# Front-End.net
KiCad netlist of a schematic drawn in EAGLE
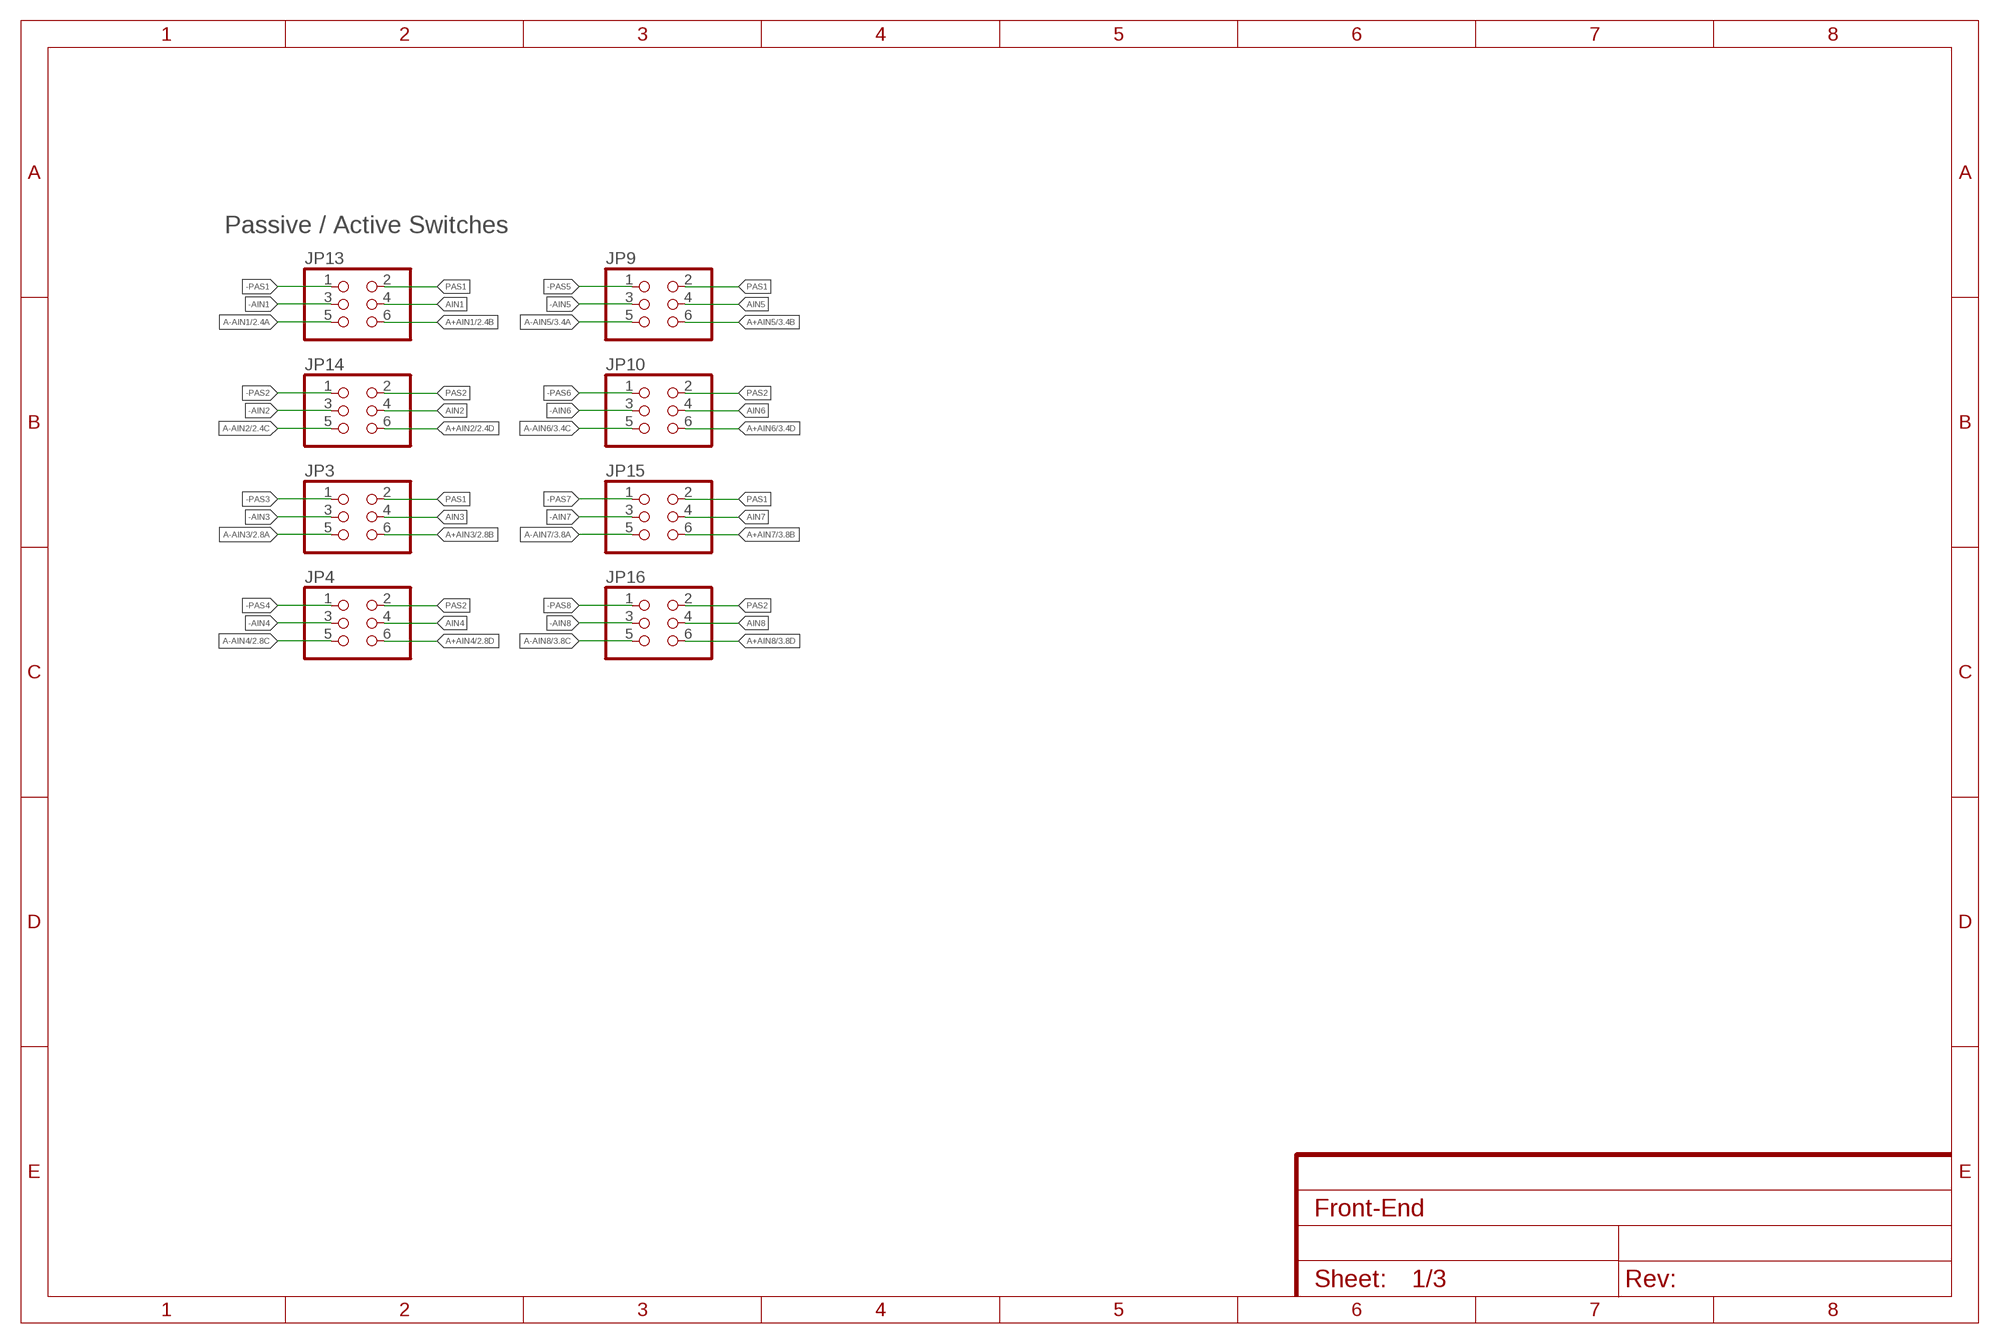
[diagram p0: schematic, sheet 1]
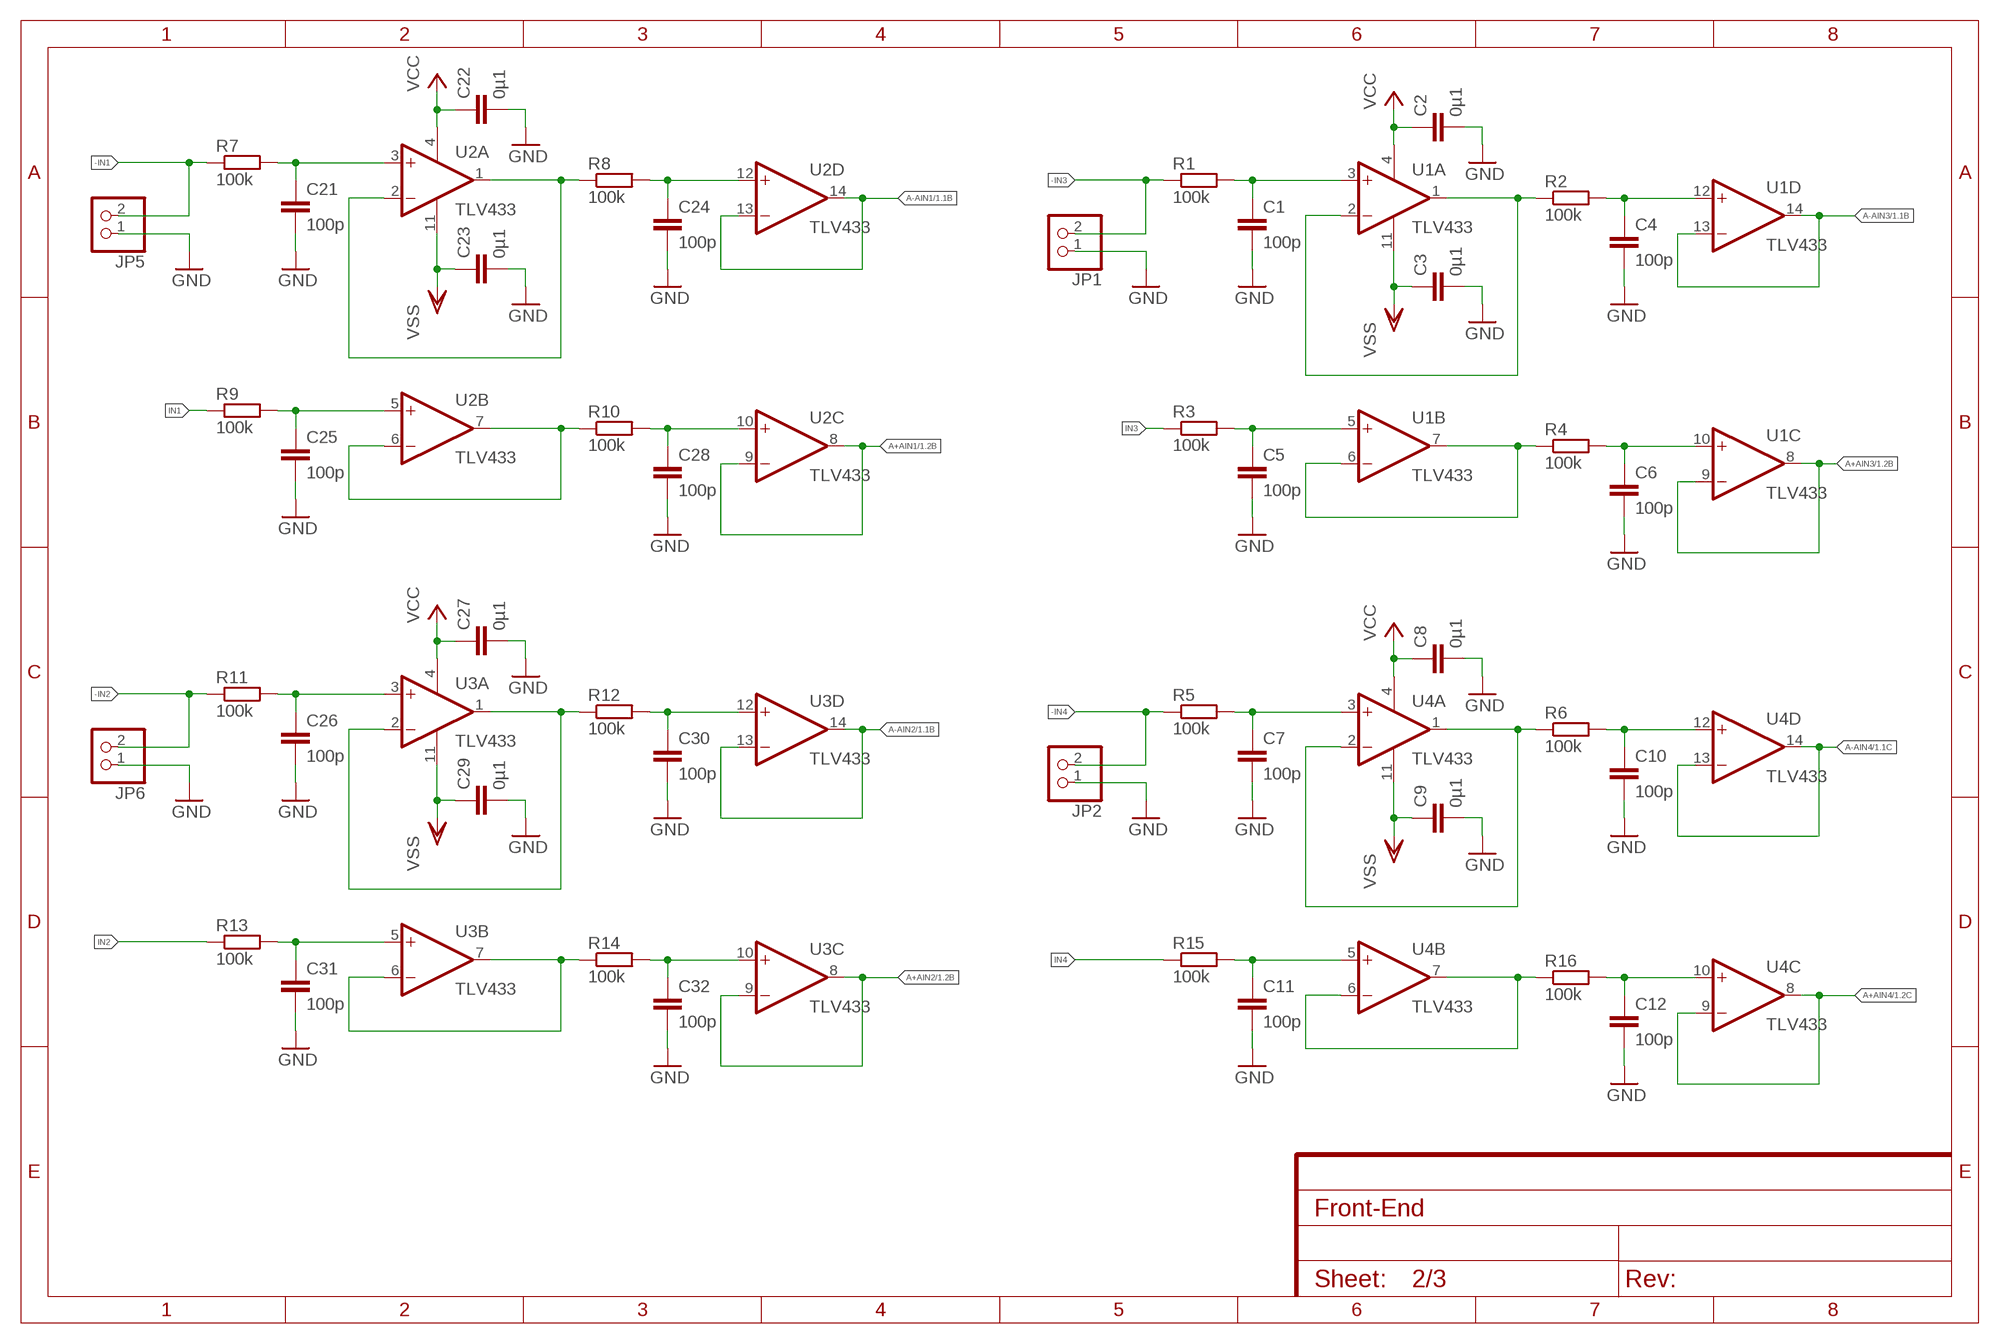
[diagram p1: schematic, sheet 2]
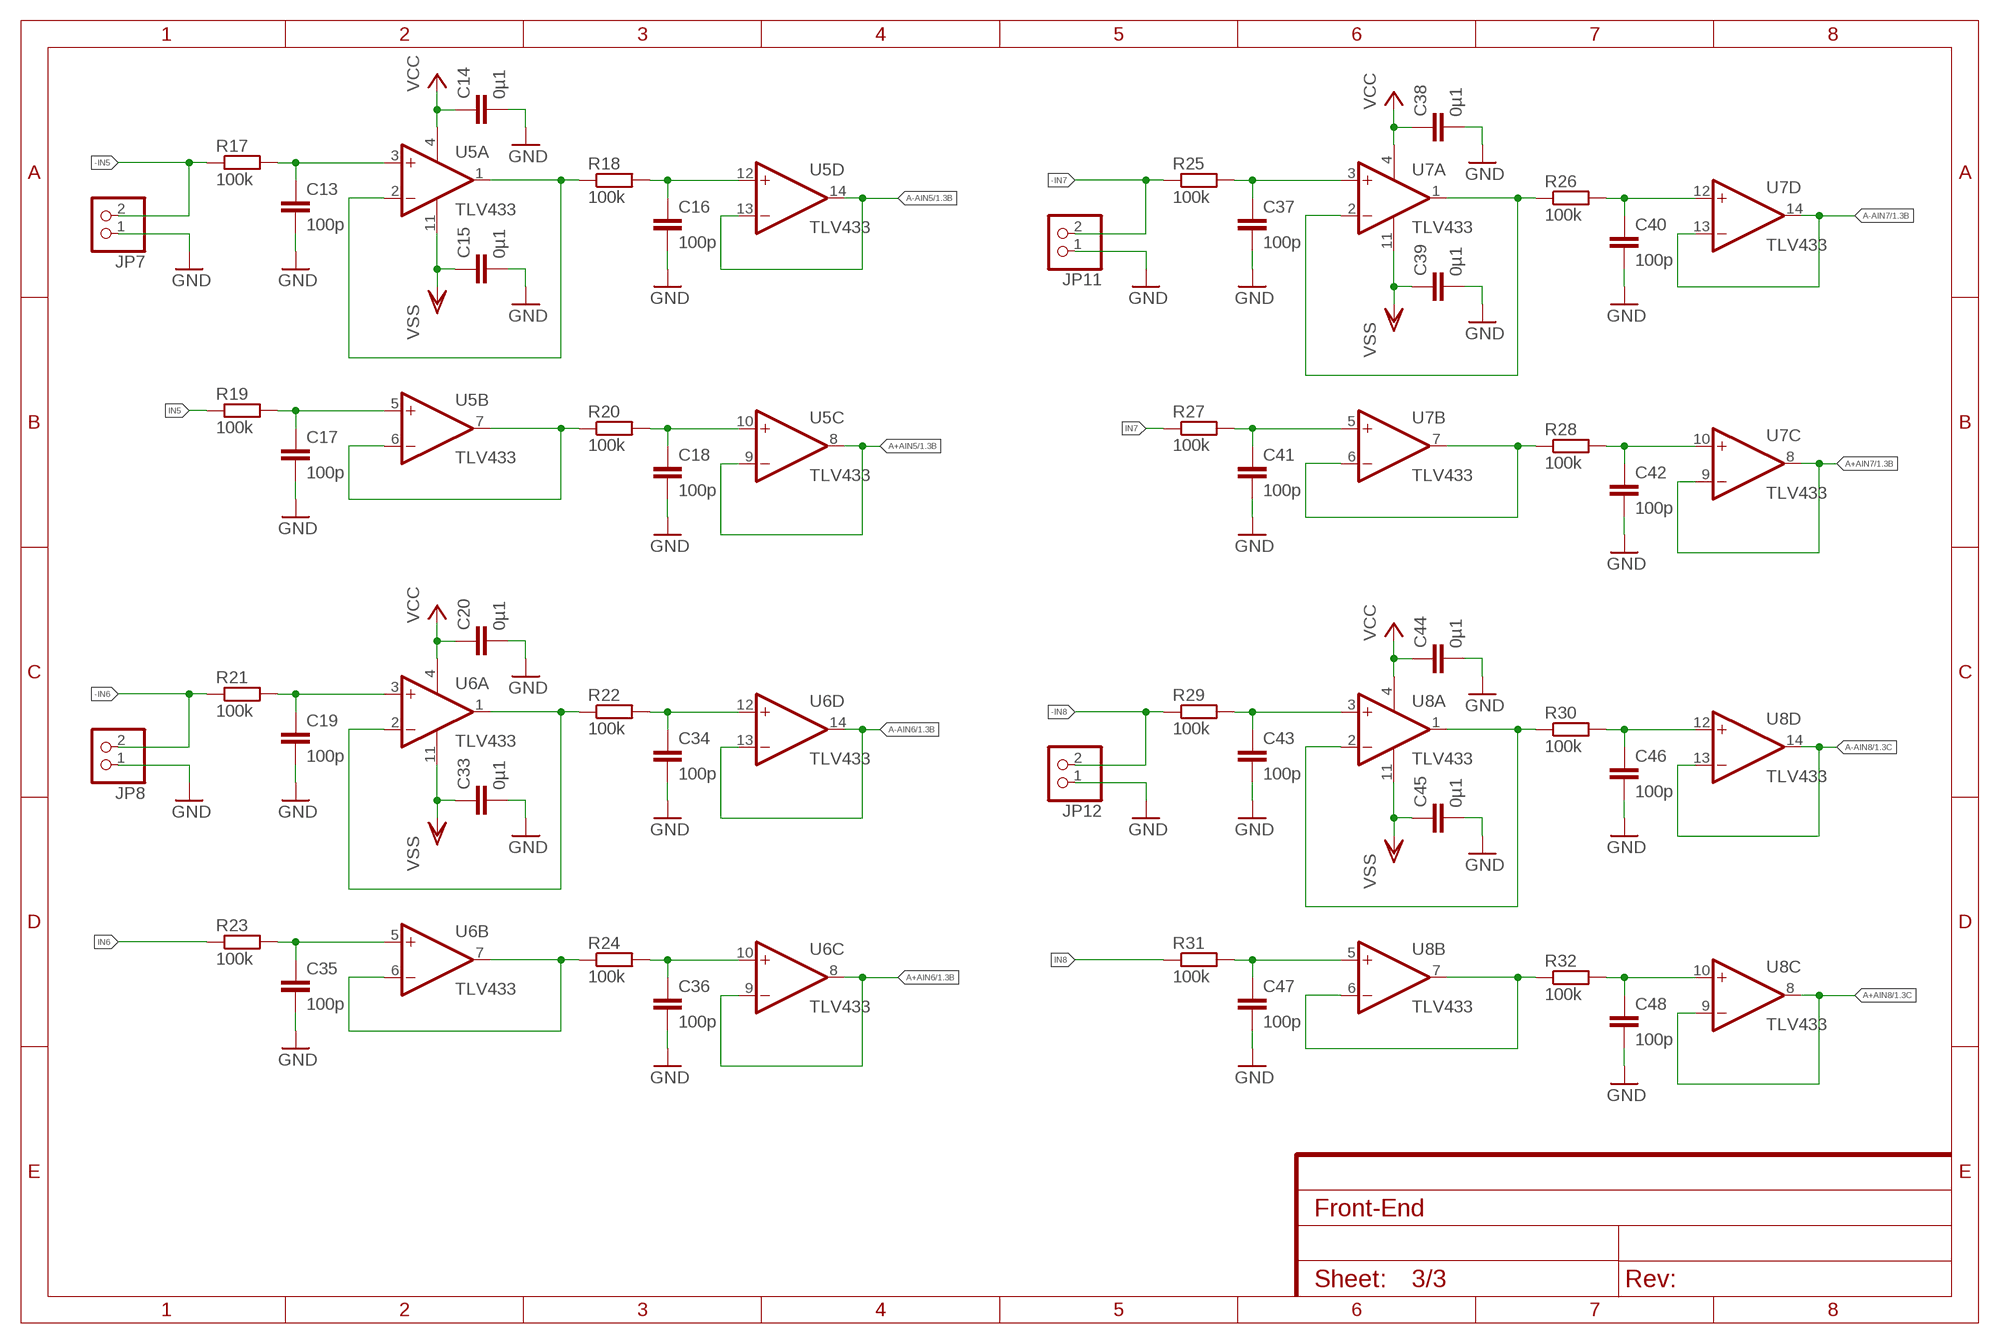
[diagram p2: schematic, sheet 3]

(export (version "E")
  (design (tool "Eeschema 10.0.6"))
  (components
    (comp (ref "C13")
      (value "100p")
      (footprint "eagle-import:C0603")
      (libsource (lib "eagle-import") (part "C-EUC0603"))
    )
    (comp (ref "C14")
      (value "0µ1")
      (footprint "eagle-import:C0603")
      (libsource (lib "eagle-import") (part "C-EUC0603"))
    )
    (comp (ref "C15")
      (value "0µ1")
      (footprint "eagle-import:C0603")
      (libsource (lib "eagle-import") (part "C-EUC0603"))
    )
    (comp (ref "C16")
      (value "100p")
      (footprint "eagle-import:C0603")
      (libsource (lib "eagle-import") (part "C-EUC0603"))
    )
    (comp (ref "C17")
      (value "100p")
      (footprint "eagle-import:C0603")
      (libsource (lib "eagle-import") (part "C-EUC0603"))
    )
    (comp (ref "C18")
      (value "100p")
      (footprint "eagle-import:C0603")
      (libsource (lib "eagle-import") (part "C-EUC0603"))
    )
    (comp (ref "C19")
      (value "100p")
      (footprint "eagle-import:C0603")
      (libsource (lib "eagle-import") (part "C-EUC0603"))
    )
    (comp (ref "C20")
      (value "0µ1")
      (footprint "eagle-import:C0603")
      (libsource (lib "eagle-import") (part "C-EUC0603"))
    )
    (comp (ref "C33")
      (value "0µ1")
      (footprint "eagle-import:C0603")
      (libsource (lib "eagle-import") (part "C-EUC0603"))
    )
    (comp (ref "C34")
      (value "100p")
      (footprint "eagle-import:C0603")
      (libsource (lib "eagle-import") (part "C-EUC0603"))
    )
    (comp (ref "C35")
      (value "100p")
      (footprint "eagle-import:C0603")
      (libsource (lib "eagle-import") (part "C-EUC0603"))
    )
    (comp (ref "C36")
      (value "100p")
      (footprint "eagle-import:C0603")
      (libsource (lib "eagle-import") (part "C-EUC0603"))
    )
    (comp (ref "C37")
      (value "100p")
      (footprint "eagle-import:C0603")
      (libsource (lib "eagle-import") (part "C-EUC0603"))
    )
    (comp (ref "C38")
      (value "0µ1")
      (footprint "eagle-import:C0603")
      (libsource (lib "eagle-import") (part "C-EUC0603"))
    )
    (comp (ref "C39")
      (value "0µ1")
      (footprint "eagle-import:C0603")
      (libsource (lib "eagle-import") (part "C-EUC0603"))
    )
    (comp (ref "C40")
      (value "100p")
      (footprint "eagle-import:C0603")
      (libsource (lib "eagle-import") (part "C-EUC0603"))
    )
    (comp (ref "C41")
      (value "100p")
      (footprint "eagle-import:C0603")
      (libsource (lib "eagle-import") (part "C-EUC0603"))
    )
    (comp (ref "C42")
      (value "100p")
      (footprint "eagle-import:C0603")
      (libsource (lib "eagle-import") (part "C-EUC0603"))
    )
    (comp (ref "C43")
      (value "100p")
      (footprint "eagle-import:C0603")
      (libsource (lib "eagle-import") (part "C-EUC0603"))
    )
    (comp (ref "C44")
      (value "0µ1")
      (footprint "eagle-import:C0603")
      (libsource (lib "eagle-import") (part "C-EUC0603"))
    )
    (comp (ref "C45")
      (value "0µ1")
      (footprint "eagle-import:C0603")
      (libsource (lib "eagle-import") (part "C-EUC0603"))
    )
    (comp (ref "C46")
      (value "100p")
      (footprint "eagle-import:C0603")
      (libsource (lib "eagle-import") (part "C-EUC0603"))
    )
    (comp (ref "C47")
      (value "100p")
      (footprint "eagle-import:C0603")
      (libsource (lib "eagle-import") (part "C-EUC0603"))
    )
    (comp (ref "C48")
      (value "100p")
      (footprint "eagle-import:C0603")
      (libsource (lib "eagle-import") (part "C-EUC0603"))
    )
    (comp (ref "JP7")
      (value "PINHD-1X2")
      (footprint "eagle-import:1X02")
      (libsource (lib "eagle-import") (part "PINHD-1X2"))
    )
    (comp (ref "JP8")
      (value "PINHD-1X2")
      (footprint "eagle-import:1X02")
      (libsource (lib "eagle-import") (part "PINHD-1X2"))
    )
    (comp (ref "JP11")
      (value "PINHD-1X2")
      (footprint "eagle-import:1X02")
      (libsource (lib "eagle-import") (part "PINHD-1X2"))
    )
    (comp (ref "JP12")
      (value "PINHD-1X2")
      (footprint "eagle-import:1X02")
      (libsource (lib "eagle-import") (part "PINHD-1X2"))
    )
    (comp (ref "R17")
      (value "100k")
      (footprint "eagle-import:R0603")
      (libsource (lib "eagle-import") (part "R-EU_R0603"))
    )
    (comp (ref "R18")
      (value "100k")
      (footprint "eagle-import:R0603")
      (libsource (lib "eagle-import") (part "R-EU_R0603"))
    )
    (comp (ref "R19")
      (value "100k")
      (footprint "eagle-import:R0603")
      (libsource (lib "eagle-import") (part "R-EU_R0603"))
    )
    (comp (ref "R20")
      (value "100k")
      (footprint "eagle-import:R0603")
      (libsource (lib "eagle-import") (part "R-EU_R0603"))
    )
    (comp (ref "R21")
      (value "100k")
      (footprint "eagle-import:R0603")
      (libsource (lib "eagle-import") (part "R-EU_R0603"))
    )
    (comp (ref "R22")
      (value "100k")
      (footprint "eagle-import:R0603")
      (libsource (lib "eagle-import") (part "R-EU_R0603"))
    )
    (comp (ref "R23")
      (value "100k")
      (footprint "eagle-import:R0603")
      (libsource (lib "eagle-import") (part "R-EU_R0603"))
    )
    (comp (ref "R24")
      (value "100k")
      (footprint "eagle-import:R0603")
      (libsource (lib "eagle-import") (part "R-EU_R0603"))
    )
    (comp (ref "R25")
      (value "100k")
      (footprint "eagle-import:R0603")
      (libsource (lib "eagle-import") (part "R-EU_R0603"))
    )
    (comp (ref "R26")
      (value "100k")
      (footprint "eagle-import:R0603")
      (libsource (lib "eagle-import") (part "R-EU_R0603"))
    )
    (comp (ref "R27")
      (value "100k")
      (footprint "eagle-import:R0603")
      (libsource (lib "eagle-import") (part "R-EU_R0603"))
    )
    (comp (ref "R28")
      (value "100k")
      (footprint "eagle-import:R0603")
      (libsource (lib "eagle-import") (part "R-EU_R0603"))
    )
    (comp (ref "R29")
      (value "100k")
      (footprint "eagle-import:R0603")
      (libsource (lib "eagle-import") (part "R-EU_R0603"))
    )
    (comp (ref "R30")
      (value "100k")
      (footprint "eagle-import:R0603")
      (libsource (lib "eagle-import") (part "R-EU_R0603"))
    )
    (comp (ref "R31")
      (value "100k")
      (footprint "eagle-import:R0603")
      (libsource (lib "eagle-import") (part "R-EU_R0603"))
    )
    (comp (ref "R32")
      (value "100k")
      (footprint "eagle-import:R0603")
      (libsource (lib "eagle-import") (part "R-EU_R0603"))
    )
    (comp (ref "U5")
      (value "TLV433")
      (footprint "eagle-import:TSSOP14")
      (libsource (lib "eagle-import") (part "TLV433"))
    )
    (comp (ref "U6")
      (value "TLV433")
      (footprint "eagle-import:TSSOP14")
      (libsource (lib "eagle-import") (part "TLV433"))
    )
    (comp (ref "U7")
      (value "TLV433")
      (footprint "eagle-import:TSSOP14")
      (libsource (lib "eagle-import") (part "TLV433"))
    )
    (comp (ref "U8")
      (value "TLV433")
      (footprint "eagle-import:TSSOP14")
      (libsource (lib "eagle-import") (part "TLV433"))
    )
    (comp (ref "C1")
      (value "100p")
      (footprint "eagle-import:C0603")
      (libsource (lib "eagle-import") (part "C-EUC0603"))
    )
    (comp (ref "C2")
      (value "0µ1")
      (footprint "eagle-import:C0603")
      (libsource (lib "eagle-import") (part "C-EUC0603"))
    )
    (comp (ref "C3")
      (value "0µ1")
      (footprint "eagle-import:C0603")
      (libsource (lib "eagle-import") (part "C-EUC0603"))
    )
    (comp (ref "C4")
      (value "100p")
      (footprint "eagle-import:C0603")
      (libsource (lib "eagle-import") (part "C-EUC0603"))
    )
    (comp (ref "C5")
      (value "100p")
      (footprint "eagle-import:C0603")
      (libsource (lib "eagle-import") (part "C-EUC0603"))
    )
    (comp (ref "C6")
      (value "100p")
      (footprint "eagle-import:C0603")
      (libsource (lib "eagle-import") (part "C-EUC0603"))
    )
    (comp (ref "C7")
      (value "100p")
      (footprint "eagle-import:C0603")
      (libsource (lib "eagle-import") (part "C-EUC0603"))
    )
    (comp (ref "C8")
      (value "0µ1")
      (footprint "eagle-import:C0603")
      (libsource (lib "eagle-import") (part "C-EUC0603"))
    )
    (comp (ref "C9")
      (value "0µ1")
      (footprint "eagle-import:C0603")
      (libsource (lib "eagle-import") (part "C-EUC0603"))
    )
    (comp (ref "C10")
      (value "100p")
      (footprint "eagle-import:C0603")
      (libsource (lib "eagle-import") (part "C-EUC0603"))
    )
    (comp (ref "C11")
      (value "100p")
      (footprint "eagle-import:C0603")
      (libsource (lib "eagle-import") (part "C-EUC0603"))
    )
    (comp (ref "C12")
      (value "100p")
      (footprint "eagle-import:C0603")
      (libsource (lib "eagle-import") (part "C-EUC0603"))
    )
    (comp (ref "C21")
      (value "100p")
      (footprint "eagle-import:C0603")
      (libsource (lib "eagle-import") (part "C-EUC0603"))
    )
    (comp (ref "C22")
      (value "0µ1")
      (footprint "eagle-import:C0603")
      (libsource (lib "eagle-import") (part "C-EUC0603"))
    )
    (comp (ref "C23")
      (value "0µ1")
      (footprint "eagle-import:C0603")
      (libsource (lib "eagle-import") (part "C-EUC0603"))
    )
    (comp (ref "C24")
      (value "100p")
      (footprint "eagle-import:C0603")
      (libsource (lib "eagle-import") (part "C-EUC0603"))
    )
    (comp (ref "C25")
      (value "100p")
      (footprint "eagle-import:C0603")
      (libsource (lib "eagle-import") (part "C-EUC0603"))
    )
    (comp (ref "C26")
      (value "100p")
      (footprint "eagle-import:C0603")
      (libsource (lib "eagle-import") (part "C-EUC0603"))
    )
    (comp (ref "C27")
      (value "0µ1")
      (footprint "eagle-import:C0603")
      (libsource (lib "eagle-import") (part "C-EUC0603"))
    )
    (comp (ref "C28")
      (value "100p")
      (footprint "eagle-import:C0603")
      (libsource (lib "eagle-import") (part "C-EUC0603"))
    )
    (comp (ref "C29")
      (value "0µ1")
      (footprint "eagle-import:C0603")
      (libsource (lib "eagle-import") (part "C-EUC0603"))
    )
    (comp (ref "C30")
      (value "100p")
      (footprint "eagle-import:C0603")
      (libsource (lib "eagle-import") (part "C-EUC0603"))
    )
    (comp (ref "C31")
      (value "100p")
      (footprint "eagle-import:C0603")
      (libsource (lib "eagle-import") (part "C-EUC0603"))
    )
    (comp (ref "C32")
      (value "100p")
      (footprint "eagle-import:C0603")
      (libsource (lib "eagle-import") (part "C-EUC0603"))
    )
    (comp (ref "JP1")
      (value "PINHD-1X2")
      (footprint "eagle-import:1X02")
      (libsource (lib "eagle-import") (part "PINHD-1X2"))
    )
    (comp (ref "JP2")
      (value "PINHD-1X2")
      (footprint "eagle-import:1X02")
      (libsource (lib "eagle-import") (part "PINHD-1X2"))
    )
    (comp (ref "JP5")
      (value "PINHD-1X2")
      (footprint "eagle-import:1X02")
      (libsource (lib "eagle-import") (part "PINHD-1X2"))
    )
    (comp (ref "JP6")
      (value "PINHD-1X2")
      (footprint "eagle-import:1X02")
      (libsource (lib "eagle-import") (part "PINHD-1X2"))
    )
    (comp (ref "R1")
      (value "100k")
      (footprint "eagle-import:R0603")
      (libsource (lib "eagle-import") (part "R-EU_R0603"))
    )
    (comp (ref "R2")
      (value "100k")
      (footprint "eagle-import:R0603")
      (libsource (lib "eagle-import") (part "R-EU_R0603"))
    )
    (comp (ref "R3")
      (value "100k")
      (footprint "eagle-import:R0603")
      (libsource (lib "eagle-import") (part "R-EU_R0603"))
    )
    (comp (ref "R4")
      (value "100k")
      (footprint "eagle-import:R0603")
      (libsource (lib "eagle-import") (part "R-EU_R0603"))
    )
    (comp (ref "R5")
      (value "100k")
      (footprint "eagle-import:R0603")
      (libsource (lib "eagle-import") (part "R-EU_R0603"))
    )
    (comp (ref "R6")
      (value "100k")
      (footprint "eagle-import:R0603")
      (libsource (lib "eagle-import") (part "R-EU_R0603"))
    )
    (comp (ref "R7")
      (value "100k")
      (footprint "eagle-import:R0603")
      (libsource (lib "eagle-import") (part "R-EU_R0603"))
    )
    (comp (ref "R8")
      (value "100k")
      (footprint "eagle-import:R0603")
      (libsource (lib "eagle-import") (part "R-EU_R0603"))
    )
    (comp (ref "R9")
      (value "100k")
      (footprint "eagle-import:R0603")
      (libsource (lib "eagle-import") (part "R-EU_R0603"))
    )
    (comp (ref "R10")
      (value "100k")
      (footprint "eagle-import:R0603")
      (libsource (lib "eagle-import") (part "R-EU_R0603"))
    )
    (comp (ref "R11")
      (value "100k")
      (footprint "eagle-import:R0603")
      (libsource (lib "eagle-import") (part "R-EU_R0603"))
    )
    (comp (ref "R12")
      (value "100k")
      (footprint "eagle-import:R0603")
      (libsource (lib "eagle-import") (part "R-EU_R0603"))
    )
    (comp (ref "R13")
      (value "100k")
      (footprint "eagle-import:R0603")
      (libsource (lib "eagle-import") (part "R-EU_R0603"))
    )
    (comp (ref "R14")
      (value "100k")
      (footprint "eagle-import:R0603")
      (libsource (lib "eagle-import") (part "R-EU_R0603"))
    )
    (comp (ref "R15")
      (value "100k")
      (footprint "eagle-import:R0603")
      (libsource (lib "eagle-import") (part "R-EU_R0603"))
    )
    (comp (ref "R16")
      (value "100k")
      (footprint "eagle-import:R0603")
      (libsource (lib "eagle-import") (part "R-EU_R0603"))
    )
    (comp (ref "U1")
      (value "TLV433")
      (footprint "eagle-import:TSSOP14")
      (libsource (lib "eagle-import") (part "TLV433"))
    )
    (comp (ref "U2")
      (value "TLV433")
      (footprint "eagle-import:TSSOP14")
      (libsource (lib "eagle-import") (part "TLV433"))
    )
    (comp (ref "U3")
      (value "TLV433")
      (footprint "eagle-import:TSSOP14")
      (libsource (lib "eagle-import") (part "TLV433"))
    )
    (comp (ref "U4")
      (value "TLV433")
      (footprint "eagle-import:TSSOP14")
      (libsource (lib "eagle-import") (part "TLV433"))
    )
    (comp (ref "JP3")
      (value "PINHD-2X3")
      (footprint "eagle-import:2X03")
      (libsource (lib "eagle-import") (part "PINHD-2X3"))
    )
    (comp (ref "JP4")
      (value "PINHD-2X3")
      (footprint "eagle-import:2X03")
      (libsource (lib "eagle-import") (part "PINHD-2X3"))
    )
    (comp (ref "JP9")
      (value "PINHD-2X3")
      (footprint "eagle-import:2X03")
      (libsource (lib "eagle-import") (part "PINHD-2X3"))
    )
    (comp (ref "JP10")
      (value "PINHD-2X3")
      (footprint "eagle-import:2X03")
      (libsource (lib "eagle-import") (part "PINHD-2X3"))
    )
    (comp (ref "JP13")
      (value "PINHD-2X3")
      (footprint "eagle-import:2X03")
      (libsource (lib "eagle-import") (part "PINHD-2X3"))
    )
    (comp (ref "JP14")
      (value "PINHD-2X3")
      (footprint "eagle-import:2X03")
      (libsource (lib "eagle-import") (part "PINHD-2X3"))
    )
    (comp (ref "JP15")
      (value "PINHD-2X3")
      (footprint "eagle-import:2X03")
      (libsource (lib "eagle-import") (part "PINHD-2X3"))
    )
    (comp (ref "JP16")
      (value "PINHD-2X3")
      (footprint "eagle-import:2X03")
      (libsource (lib "eagle-import") (part "PINHD-2X3"))
    )
  )
  (nets
    (net (code "1") (name "-AIN1") (class "Default")
      (node (ref "JP13") (pin "3") (pinfunction "3_3") (pintype "passive"))
    )
    (net (code "2") (name "-AIN2") (class "Default")
      (node (ref "JP14") (pin "3") (pinfunction "3_3") (pintype "passive"))
    )
    (net (code "3") (name "-AIN3") (class "Default")
      (node (ref "JP3") (pin "3") (pinfunction "3_3") (pintype "passive"))
    )
    (net (code "4") (name "-AIN4") (class "Default")
      (node (ref "JP4") (pin "3") (pinfunction "3_3") (pintype "passive"))
    )
    (net (code "5") (name "-AIN5") (class "Default")
      (node (ref "JP9") (pin "3") (pinfunction "3_3") (pintype "passive"))
    )
    (net (code "6") (name "-AIN6") (class "Default")
      (node (ref "JP10") (pin "3") (pinfunction "3_3") (pintype "passive"))
    )
    (net (code "7") (name "-AIN7") (class "Default")
      (node (ref "JP15") (pin "3") (pinfunction "3_3") (pintype "passive"))
    )
    (net (code "8") (name "-AIN8") (class "Default")
      (node (ref "JP16") (pin "3") (pinfunction "3_3") (pintype "passive"))
    )
    (net (code "9") (name "-IN1") (class "Default")
      (node (ref "JP5") (pin "2") (pinfunction "2_2") (pintype "passive"))
      (node (ref "R7") (pin "1") (pinfunction "1_1") (pintype "passive"))
    )
    (net (code "10") (name "-IN2") (class "Default")
      (node (ref "JP6") (pin "2") (pinfunction "2_2") (pintype "passive"))
      (node (ref "R11") (pin "1") (pinfunction "1_1") (pintype "passive"))
    )
    (net (code "11") (name "-IN3") (class "Default")
      (node (ref "JP1") (pin "2") (pinfunction "2_2") (pintype "passive"))
      (node (ref "R1") (pin "1") (pinfunction "1_1") (pintype "passive"))
    )
    (net (code "12") (name "-IN4") (class "Default")
      (node (ref "JP2") (pin "2") (pinfunction "2_2") (pintype "passive"))
      (node (ref "R5") (pin "1") (pinfunction "1_1") (pintype "passive"))
    )
    (net (code "13") (name "-IN5") (class "Default")
      (node (ref "JP7") (pin "2") (pinfunction "2_2") (pintype "passive"))
      (node (ref "R17") (pin "1") (pinfunction "1_1") (pintype "passive"))
    )
    (net (code "14") (name "-IN6") (class "Default")
      (node (ref "JP8") (pin "2") (pinfunction "2_2") (pintype "passive"))
      (node (ref "R21") (pin "1") (pinfunction "1_1") (pintype "passive"))
    )
    (net (code "15") (name "-IN7") (class "Default")
      (node (ref "JP11") (pin "2") (pinfunction "2_2") (pintype "passive"))
      (node (ref "R25") (pin "1") (pinfunction "1_1") (pintype "passive"))
    )
    (net (code "16") (name "-IN8") (class "Default")
      (node (ref "JP12") (pin "2") (pinfunction "2_2") (pintype "passive"))
      (node (ref "R29") (pin "1") (pinfunction "1_1") (pintype "passive"))
    )
    (net (code "17") (name "-PAS1") (class "Default")
      (node (ref "C21") (pin "1") (pinfunction "1_1") (pintype "passive"))
      (node (ref "JP13") (pin "1") (pinfunction "1_1") (pintype "passive"))
      (node (ref "R7") (pin "2") (pinfunction "2_2") (pintype "passive"))
      (node (ref "U2") (pin "3") (pinfunction "+IN_3") (pintype "input"))
    )
    (net (code "18") (name "-PAS2") (class "Default")
      (node (ref "C26") (pin "1") (pinfunction "1_1") (pintype "passive"))
      (node (ref "JP14") (pin "1") (pinfunction "1_1") (pintype "passive"))
      (node (ref "R11") (pin "2") (pinfunction "2_2") (pintype "passive"))
      (node (ref "U3") (pin "3") (pinfunction "+IN_3") (pintype "input"))
    )
    (net (code "19") (name "-PAS3") (class "Default")
      (node (ref "C1") (pin "1") (pinfunction "1_1") (pintype "passive"))
      (node (ref "JP3") (pin "1") (pinfunction "1_1") (pintype "passive"))
      (node (ref "R1") (pin "2") (pinfunction "2_2") (pintype "passive"))
      (node (ref "U1") (pin "3") (pinfunction "+IN_3") (pintype "input"))
    )
    (net (code "20") (name "-PAS4") (class "Default")
      (node (ref "C7") (pin "1") (pinfunction "1_1") (pintype "passive"))
      (node (ref "JP4") (pin "1") (pinfunction "1_1") (pintype "passive"))
      (node (ref "R5") (pin "2") (pinfunction "2_2") (pintype "passive"))
      (node (ref "U4") (pin "3") (pinfunction "+IN_3") (pintype "input"))
    )
    (net (code "21") (name "-PAS5") (class "Default")
      (node (ref "C13") (pin "1") (pinfunction "1_1") (pintype "passive"))
      (node (ref "JP9") (pin "1") (pinfunction "1_1") (pintype "passive"))
      (node (ref "R17") (pin "2") (pinfunction "2_2") (pintype "passive"))
      (node (ref "U5") (pin "3") (pinfunction "+IN_3") (pintype "input"))
    )
    (net (code "22") (name "-PAS6") (class "Default")
      (node (ref "C19") (pin "1") (pinfunction "1_1") (pintype "passive"))
      (node (ref "JP10") (pin "1") (pinfunction "1_1") (pintype "passive"))
      (node (ref "R21") (pin "2") (pinfunction "2_2") (pintype "passive"))
      (node (ref "U6") (pin "3") (pinfunction "+IN_3") (pintype "input"))
    )
    (net (code "23") (name "-PAS7") (class "Default")
      (node (ref "C37") (pin "1") (pinfunction "1_1") (pintype "passive"))
      (node (ref "JP15") (pin "1") (pinfunction "1_1") (pintype "passive"))
      (node (ref "R25") (pin "2") (pinfunction "2_2") (pintype "passive"))
      (node (ref "U7") (pin "3") (pinfunction "+IN_3") (pintype "input"))
    )
    (net (code "24") (name "-PAS8") (class "Default")
      (node (ref "C43") (pin "1") (pinfunction "1_1") (pintype "passive"))
      (node (ref "JP16") (pin "1") (pinfunction "1_1") (pintype "passive"))
      (node (ref "R29") (pin "2") (pinfunction "2_2") (pintype "passive"))
      (node (ref "U8") (pin "3") (pinfunction "+IN_3") (pintype "input"))
    )
    (net (code "25") (name "A+AIN1") (class "Default")
      (node (ref "JP13") (pin "6") (pinfunction "6_6") (pintype "passive"))
      (node (ref "U2") (pin "8") (pinfunction "OUT_8") (pintype "output"))
      (node (ref "U2") (pin "9") (pinfunction "-IN_9") (pintype "input"))
    )
    (net (code "26") (name "A+AIN2") (class "Default")
      (node (ref "JP14") (pin "6") (pinfunction "6_6") (pintype "passive"))
      (node (ref "U3") (pin "8") (pinfunction "OUT_8") (pintype "output"))
      (node (ref "U3") (pin "9") (pinfunction "-IN_9") (pintype "input"))
    )
    (net (code "27") (name "A+AIN3") (class "Default")
      (node (ref "JP3") (pin "6") (pinfunction "6_6") (pintype "passive"))
      (node (ref "U1") (pin "8") (pinfunction "OUT_8") (pintype "output"))
      (node (ref "U1") (pin "9") (pinfunction "-IN_9") (pintype "input"))
    )
    (net (code "28") (name "A+AIN4") (class "Default")
      (node (ref "JP4") (pin "6") (pinfunction "6_6") (pintype "passive"))
      (node (ref "U4") (pin "8") (pinfunction "OUT_8") (pintype "output"))
      (node (ref "U4") (pin "9") (pinfunction "-IN_9") (pintype "input"))
    )
    (net (code "29") (name "A+AIN5") (class "Default")
      (node (ref "JP9") (pin "6") (pinfunction "6_6") (pintype "passive"))
      (node (ref "U5") (pin "8") (pinfunction "OUT_8") (pintype "output"))
      (node (ref "U5") (pin "9") (pinfunction "-IN_9") (pintype "input"))
    )
    (net (code "30") (name "A+AIN6") (class "Default")
      (node (ref "JP10") (pin "6") (pinfunction "6_6") (pintype "passive"))
      (node (ref "U6") (pin "8") (pinfunction "OUT_8") (pintype "output"))
      (node (ref "U6") (pin "9") (pinfunction "-IN_9") (pintype "input"))
    )
    (net (code "31") (name "A+AIN7") (class "Default")
      (node (ref "JP15") (pin "6") (pinfunction "6_6") (pintype "passive"))
      (node (ref "U7") (pin "8") (pinfunction "OUT_8") (pintype "output"))
      (node (ref "U7") (pin "9") (pinfunction "-IN_9") (pintype "input"))
    )
    (net (code "32") (name "A+AIN8") (class "Default")
      (node (ref "JP16") (pin "6") (pinfunction "6_6") (pintype "passive"))
      (node (ref "U8") (pin "8") (pinfunction "OUT_8") (pintype "output"))
      (node (ref "U8") (pin "9") (pinfunction "-IN_9") (pintype "input"))
    )
    (net (code "33") (name "A-AIN1") (class "Default")
      (node (ref "JP13") (pin "5") (pinfunction "5_5") (pintype "passive"))
      (node (ref "U2") (pin "13") (pinfunction "-IN_13") (pintype "input"))
      (node (ref "U2") (pin "14") (pinfunction "OUT_14") (pintype "output"))
    )
    (net (code "34") (name "A-AIN2") (class "Default")
      (node (ref "JP14") (pin "5") (pinfunction "5_5") (pintype "passive"))
      (node (ref "U3") (pin "13") (pinfunction "-IN_13") (pintype "input"))
      (node (ref "U3") (pin "14") (pinfunction "OUT_14") (pintype "output"))
    )
    (net (code "35") (name "A-AIN3") (class "Default")
      (node (ref "JP3") (pin "5") (pinfunction "5_5") (pintype "passive"))
      (node (ref "U1") (pin "13") (pinfunction "-IN_13") (pintype "input"))
      (node (ref "U1") (pin "14") (pinfunction "OUT_14") (pintype "output"))
    )
    (net (code "36") (name "A-AIN4") (class "Default")
      (node (ref "JP4") (pin "5") (pinfunction "5_5") (pintype "passive"))
      (node (ref "U4") (pin "13") (pinfunction "-IN_13") (pintype "input"))
      (node (ref "U4") (pin "14") (pinfunction "OUT_14") (pintype "output"))
    )
    (net (code "37") (name "A-AIN5") (class "Default")
      (node (ref "JP9") (pin "5") (pinfunction "5_5") (pintype "passive"))
      (node (ref "U5") (pin "13") (pinfunction "-IN_13") (pintype "input"))
      (node (ref "U5") (pin "14") (pinfunction "OUT_14") (pintype "output"))
    )
    (net (code "38") (name "A-AIN6") (class "Default")
      (node (ref "JP10") (pin "5") (pinfunction "5_5") (pintype "passive"))
      (node (ref "U6") (pin "13") (pinfunction "-IN_13") (pintype "input"))
      (node (ref "U6") (pin "14") (pinfunction "OUT_14") (pintype "output"))
    )
    (net (code "39") (name "A-AIN7") (class "Default")
      (node (ref "JP15") (pin "5") (pinfunction "5_5") (pintype "passive"))
      (node (ref "U7") (pin "13") (pinfunction "-IN_13") (pintype "input"))
      (node (ref "U7") (pin "14") (pinfunction "OUT_14") (pintype "output"))
    )
    (net (code "40") (name "A-AIN8") (class "Default")
      (node (ref "JP16") (pin "5") (pinfunction "5_5") (pintype "passive"))
      (node (ref "U8") (pin "13") (pinfunction "-IN_13") (pintype "input"))
      (node (ref "U8") (pin "14") (pinfunction "OUT_14") (pintype "output"))
    )
    (net (code "41") (name "AIN1") (class "Default")
      (node (ref "JP13") (pin "4") (pinfunction "4_4") (pintype "passive"))
    )
    (net (code "42") (name "AIN2") (class "Default")
      (node (ref "JP14") (pin "4") (pinfunction "4_4") (pintype "passive"))
    )
    (net (code "43") (name "AIN3") (class "Default")
      (node (ref "JP3") (pin "4") (pinfunction "4_4") (pintype "passive"))
    )
    (net (code "44") (name "AIN4") (class "Default")
      (node (ref "JP4") (pin "4") (pinfunction "4_4") (pintype "passive"))
    )
    (net (code "45") (name "AIN5") (class "Default")
      (node (ref "JP9") (pin "4") (pinfunction "4_4") (pintype "passive"))
    )
    (net (code "46") (name "AIN6") (class "Default")
      (node (ref "JP10") (pin "4") (pinfunction "4_4") (pintype "passive"))
    )
    (net (code "47") (name "AIN7") (class "Default")
      (node (ref "JP15") (pin "4") (pinfunction "4_4") (pintype "passive"))
    )
    (net (code "48") (name "AIN8") (class "Default")
      (node (ref "JP16") (pin "4") (pinfunction "4_4") (pintype "passive"))
    )
    (net (code "49") (name "GND") (class "Default")
      (node (ref "C1") (pin "2") (pinfunction "2_2") (pintype "passive"))
      (node (ref "C10") (pin "2") (pinfunction "2_2") (pintype "passive"))
      (node (ref "C11") (pin "2") (pinfunction "2_2") (pintype "passive"))
      (node (ref "C12") (pin "2") (pinfunction "2_2") (pintype "passive"))
      (node (ref "C13") (pin "2") (pinfunction "2_2") (pintype "passive"))
      (node (ref "C14") (pin "2") (pinfunction "2_2") (pintype "passive"))
      (node (ref "C15") (pin "2") (pinfunction "2_2") (pintype "passive"))
      (node (ref "C16") (pin "2") (pinfunction "2_2") (pintype "passive"))
      (node (ref "C17") (pin "2") (pinfunction "2_2") (pintype "passive"))
      (node (ref "C18") (pin "2") (pinfunction "2_2") (pintype "passive"))
      (node (ref "C19") (pin "2") (pinfunction "2_2") (pintype "passive"))
      (node (ref "C2") (pin "2") (pinfunction "2_2") (pintype "passive"))
      (node (ref "C20") (pin "2") (pinfunction "2_2") (pintype "passive"))
      (node (ref "C21") (pin "2") (pinfunction "2_2") (pintype "passive"))
      (node (ref "C22") (pin "2") (pinfunction "2_2") (pintype "passive"))
      (node (ref "C23") (pin "2") (pinfunction "2_2") (pintype "passive"))
      (node (ref "C24") (pin "2") (pinfunction "2_2") (pintype "passive"))
      (node (ref "C25") (pin "2") (pinfunction "2_2") (pintype "passive"))
      (node (ref "C26") (pin "2") (pinfunction "2_2") (pintype "passive"))
      (node (ref "C27") (pin "2") (pinfunction "2_2") (pintype "passive"))
      (node (ref "C28") (pin "2") (pinfunction "2_2") (pintype "passive"))
      (node (ref "C29") (pin "2") (pinfunction "2_2") (pintype "passive"))
      (node (ref "C3") (pin "2") (pinfunction "2_2") (pintype "passive"))
      (node (ref "C30") (pin "2") (pinfunction "2_2") (pintype "passive"))
      (node (ref "C31") (pin "2") (pinfunction "2_2") (pintype "passive"))
      (node (ref "C32") (pin "2") (pinfunction "2_2") (pintype "passive"))
      (node (ref "C33") (pin "2") (pinfunction "2_2") (pintype "passive"))
      (node (ref "C34") (pin "2") (pinfunction "2_2") (pintype "passive"))
      (node (ref "C35") (pin "2") (pinfunction "2_2") (pintype "passive"))
      (node (ref "C36") (pin "2") (pinfunction "2_2") (pintype "passive"))
      (node (ref "C37") (pin "2") (pinfunction "2_2") (pintype "passive"))
      (node (ref "C38") (pin "2") (pinfunction "2_2") (pintype "passive"))
      (node (ref "C39") (pin "2") (pinfunction "2_2") (pintype "passive"))
      (node (ref "C4") (pin "2") (pinfunction "2_2") (pintype "passive"))
      (node (ref "C40") (pin "2") (pinfunction "2_2") (pintype "passive"))
      (node (ref "C41") (pin "2") (pinfunction "2_2") (pintype "passive"))
      (node (ref "C42") (pin "2") (pinfunction "2_2") (pintype "passive"))
      (node (ref "C43") (pin "2") (pinfunction "2_2") (pintype "passive"))
      (node (ref "C44") (pin "2") (pinfunction "2_2") (pintype "passive"))
      (node (ref "C45") (pin "2") (pinfunction "2_2") (pintype "passive"))
      (node (ref "C46") (pin "2") (pinfunction "2_2") (pintype "passive"))
      (node (ref "C47") (pin "2") (pinfunction "2_2") (pintype "passive"))
      (node (ref "C48") (pin "2") (pinfunction "2_2") (pintype "passive"))
      (node (ref "C5") (pin "2") (pinfunction "2_2") (pintype "passive"))
      (node (ref "C6") (pin "2") (pinfunction "2_2") (pintype "passive"))
      (node (ref "C7") (pin "2") (pinfunction "2_2") (pintype "passive"))
      (node (ref "C8") (pin "2") (pinfunction "2_2") (pintype "passive"))
      (node (ref "C9") (pin "2") (pinfunction "2_2") (pintype "passive"))
      (node (ref "JP1") (pin "1") (pinfunction "1_1") (pintype "passive"))
      (node (ref "JP11") (pin "1") (pinfunction "1_1") (pintype "passive"))
      (node (ref "JP12") (pin "1") (pinfunction "1_1") (pintype "passive"))
      (node (ref "JP2") (pin "1") (pinfunction "1_1") (pintype "passive"))
      (node (ref "JP5") (pin "1") (pinfunction "1_1") (pintype "passive"))
      (node (ref "JP6") (pin "1") (pinfunction "1_1") (pintype "passive"))
      (node (ref "JP7") (pin "1") (pinfunction "1_1") (pintype "passive"))
      (node (ref "JP8") (pin "1") (pinfunction "1_1") (pintype "passive"))
    )
    (net (code "50") (name "IN1") (class "Default")
      (node (ref "R9") (pin "1") (pinfunction "1_1") (pintype "passive"))
    )
    (net (code "51") (name "IN2") (class "Default")
      (node (ref "R13") (pin "1") (pinfunction "1_1") (pintype "passive"))
    )
    (net (code "52") (name "IN3") (class "Default")
      (node (ref "R3") (pin "1") (pinfunction "1_1") (pintype "passive"))
    )
    (net (code "53") (name "IN4") (class "Default")
      (node (ref "R15") (pin "1") (pinfunction "1_1") (pintype "passive"))
    )
    (net (code "54") (name "IN5") (class "Default")
      (node (ref "R19") (pin "1") (pinfunction "1_1") (pintype "passive"))
    )
    (net (code "55") (name "IN6") (class "Default")
      (node (ref "R23") (pin "1") (pinfunction "1_1") (pintype "passive"))
    )
    (net (code "56") (name "IN7") (class "Default")
      (node (ref "R27") (pin "1") (pinfunction "1_1") (pintype "passive"))
    )
    (net (code "57") (name "IN8") (class "Default")
      (node (ref "R31") (pin "1") (pinfunction "1_1") (pintype "passive"))
    )
    (net (code "58") (name "Net-(U1A--IN)") (class "Default")
      (node (ref "R2") (pin "1") (pinfunction "1_1") (pintype "passive"))
      (node (ref "U1") (pin "1") (pinfunction "OUT_1") (pintype "output"))
      (node (ref "U1") (pin "2") (pinfunction "-IN_2") (pintype "input"))
    )
    (net (code "59") (name "Net-(U1B--IN)") (class "Default")
      (node (ref "R4") (pin "1") (pinfunction "1_1") (pintype "passive"))
      (node (ref "U1") (pin "6") (pinfunction "-IN_6") (pintype "input"))
      (node (ref "U1") (pin "7") (pinfunction "OUT_7") (pintype "output"))
    )
    (net (code "60") (name "Net-(U1C-+IN)") (class "Default")
      (node (ref "C6") (pin "1") (pinfunction "1_1") (pintype "passive"))
      (node (ref "R4") (pin "2") (pinfunction "2_2") (pintype "passive"))
      (node (ref "U1") (pin "10") (pinfunction "+IN_10") (pintype "input"))
    )
    (net (code "61") (name "Net-(U1D-+IN)") (class "Default")
      (node (ref "C4") (pin "1") (pinfunction "1_1") (pintype "passive"))
      (node (ref "R2") (pin "2") (pinfunction "2_2") (pintype "passive"))
      (node (ref "U1") (pin "12") (pinfunction "+IN_12") (pintype "input"))
    )
    (net (code "62") (name "Net-(U2A--IN)") (class "Default")
      (node (ref "R8") (pin "1") (pinfunction "1_1") (pintype "passive"))
      (node (ref "U2") (pin "1") (pinfunction "OUT_1") (pintype "output"))
      (node (ref "U2") (pin "2") (pinfunction "-IN_2") (pintype "input"))
    )
    (net (code "63") (name "Net-(U2B--IN)") (class "Default")
      (node (ref "R10") (pin "1") (pinfunction "1_1") (pintype "passive"))
      (node (ref "U2") (pin "6") (pinfunction "-IN_6") (pintype "input"))
      (node (ref "U2") (pin "7") (pinfunction "OUT_7") (pintype "output"))
    )
    (net (code "64") (name "Net-(U2C-+IN)") (class "Default")
      (node (ref "C28") (pin "1") (pinfunction "1_1") (pintype "passive"))
      (node (ref "R10") (pin "2") (pinfunction "2_2") (pintype "passive"))
      (node (ref "U2") (pin "10") (pinfunction "+IN_10") (pintype "input"))
    )
    (net (code "65") (name "Net-(U2D-+IN)") (class "Default")
      (node (ref "C24") (pin "1") (pinfunction "1_1") (pintype "passive"))
      (node (ref "R8") (pin "2") (pinfunction "2_2") (pintype "passive"))
      (node (ref "U2") (pin "12") (pinfunction "+IN_12") (pintype "input"))
    )
    (net (code "66") (name "Net-(U3A--IN)") (class "Default")
      (node (ref "R12") (pin "1") (pinfunction "1_1") (pintype "passive"))
      (node (ref "U3") (pin "1") (pinfunction "OUT_1") (pintype "output"))
      (node (ref "U3") (pin "2") (pinfunction "-IN_2") (pintype "input"))
    )
    (net (code "67") (name "Net-(U3B--IN)") (class "Default")
      (node (ref "R14") (pin "1") (pinfunction "1_1") (pintype "passive"))
      (node (ref "U3") (pin "6") (pinfunction "-IN_6") (pintype "input"))
      (node (ref "U3") (pin "7") (pinfunction "OUT_7") (pintype "output"))
    )
    (net (code "68") (name "Net-(U3C-+IN)") (class "Default")
      (node (ref "C32") (pin "1") (pinfunction "1_1") (pintype "passive"))
      (node (ref "R14") (pin "2") (pinfunction "2_2") (pintype "passive"))
      (node (ref "U3") (pin "10") (pinfunction "+IN_10") (pintype "input"))
    )
    (net (code "69") (name "Net-(U3D-+IN)") (class "Default")
      (node (ref "C30") (pin "1") (pinfunction "1_1") (pintype "passive"))
      (node (ref "R12") (pin "2") (pinfunction "2_2") (pintype "passive"))
      (node (ref "U3") (pin "12") (pinfunction "+IN_12") (pintype "input"))
    )
    (net (code "70") (name "Net-(U4A--IN)") (class "Default")
      (node (ref "R6") (pin "1") (pinfunction "1_1") (pintype "passive"))
      (node (ref "U4") (pin "1") (pinfunction "OUT_1") (pintype "output"))
      (node (ref "U4") (pin "2") (pinfunction "-IN_2") (pintype "input"))
    )
    (net (code "71") (name "Net-(U4B--IN)") (class "Default")
      (node (ref "R16") (pin "1") (pinfunction "1_1") (pintype "passive"))
      (node (ref "U4") (pin "6") (pinfunction "-IN_6") (pintype "input"))
      (node (ref "U4") (pin "7") (pinfunction "OUT_7") (pintype "output"))
    )
    (net (code "72") (name "Net-(U4C-+IN)") (class "Default")
      (node (ref "C12") (pin "1") (pinfunction "1_1") (pintype "passive"))
      (node (ref "R16") (pin "2") (pinfunction "2_2") (pintype "passive"))
      (node (ref "U4") (pin "10") (pinfunction "+IN_10") (pintype "input"))
    )
    (net (code "73") (name "Net-(U4D-+IN)") (class "Default")
      (node (ref "C10") (pin "1") (pinfunction "1_1") (pintype "passive"))
      (node (ref "R6") (pin "2") (pinfunction "2_2") (pintype "passive"))
      (node (ref "U4") (pin "12") (pinfunction "+IN_12") (pintype "input"))
    )
    (net (code "74") (name "Net-(U5A--IN)") (class "Default")
      (node (ref "R18") (pin "1") (pinfunction "1_1") (pintype "passive"))
      (node (ref "U5") (pin "1") (pinfunction "OUT_1") (pintype "output"))
      (node (ref "U5") (pin "2") (pinfunction "-IN_2") (pintype "input"))
    )
    (net (code "75") (name "Net-(U5B--IN)") (class "Default")
      (node (ref "R20") (pin "1") (pinfunction "1_1") (pintype "passive"))
      (node (ref "U5") (pin "6") (pinfunction "-IN_6") (pintype "input"))
      (node (ref "U5") (pin "7") (pinfunction "OUT_7") (pintype "output"))
    )
    (net (code "76") (name "Net-(U5C-+IN)") (class "Default")
      (node (ref "C18") (pin "1") (pinfunction "1_1") (pintype "passive"))
      (node (ref "R20") (pin "2") (pinfunction "2_2") (pintype "passive"))
      (node (ref "U5") (pin "10") (pinfunction "+IN_10") (pintype "input"))
    )
    (net (code "77") (name "Net-(U5D-+IN)") (class "Default")
      (node (ref "C16") (pin "1") (pinfunction "1_1") (pintype "passive"))
      (node (ref "R18") (pin "2") (pinfunction "2_2") (pintype "passive"))
      (node (ref "U5") (pin "12") (pinfunction "+IN_12") (pintype "input"))
    )
    (net (code "78") (name "Net-(U6A--IN)") (class "Default")
      (node (ref "R22") (pin "1") (pinfunction "1_1") (pintype "passive"))
      (node (ref "U6") (pin "1") (pinfunction "OUT_1") (pintype "output"))
      (node (ref "U6") (pin "2") (pinfunction "-IN_2") (pintype "input"))
    )
    (net (code "79") (name "Net-(U6B--IN)") (class "Default")
      (node (ref "R24") (pin "1") (pinfunction "1_1") (pintype "passive"))
      (node (ref "U6") (pin "6") (pinfunction "-IN_6") (pintype "input"))
      (node (ref "U6") (pin "7") (pinfunction "OUT_7") (pintype "output"))
    )
    (net (code "80") (name "Net-(U6C-+IN)") (class "Default")
      (node (ref "C36") (pin "1") (pinfunction "1_1") (pintype "passive"))
      (node (ref "R24") (pin "2") (pinfunction "2_2") (pintype "passive"))
      (node (ref "U6") (pin "10") (pinfunction "+IN_10") (pintype "input"))
    )
    (net (code "81") (name "Net-(U6D-+IN)") (class "Default")
      (node (ref "C34") (pin "1") (pinfunction "1_1") (pintype "passive"))
      (node (ref "R22") (pin "2") (pinfunction "2_2") (pintype "passive"))
      (node (ref "U6") (pin "12") (pinfunction "+IN_12") (pintype "input"))
    )
    (net (code "82") (name "Net-(U7A--IN)") (class "Default")
      (node (ref "R26") (pin "1") (pinfunction "1_1") (pintype "passive"))
      (node (ref "U7") (pin "1") (pinfunction "OUT_1") (pintype "output"))
      (node (ref "U7") (pin "2") (pinfunction "-IN_2") (pintype "input"))
    )
    (net (code "83") (name "Net-(U7B--IN)") (class "Default")
      (node (ref "R28") (pin "1") (pinfunction "1_1") (pintype "passive"))
      (node (ref "U7") (pin "6") (pinfunction "-IN_6") (pintype "input"))
      (node (ref "U7") (pin "7") (pinfunction "OUT_7") (pintype "output"))
    )
    (net (code "84") (name "Net-(U7C-+IN)") (class "Default")
      (node (ref "C42") (pin "1") (pinfunction "1_1") (pintype "passive"))
      (node (ref "R28") (pin "2") (pinfunction "2_2") (pintype "passive"))
      (node (ref "U7") (pin "10") (pinfunction "+IN_10") (pintype "input"))
    )
    (net (code "85") (name "Net-(U7D-+IN)") (class "Default")
      (node (ref "C40") (pin "1") (pinfunction "1_1") (pintype "passive"))
      (node (ref "R26") (pin "2") (pinfunction "2_2") (pintype "passive"))
      (node (ref "U7") (pin "12") (pinfunction "+IN_12") (pintype "input"))
    )
    (net (code "86") (name "Net-(U8A--IN)") (class "Default")
      (node (ref "R30") (pin "1") (pinfunction "1_1") (pintype "passive"))
      (node (ref "U8") (pin "1") (pinfunction "OUT_1") (pintype "output"))
      (node (ref "U8") (pin "2") (pinfunction "-IN_2") (pintype "input"))
    )
    (net (code "87") (name "Net-(U8B--IN)") (class "Default")
      (node (ref "R32") (pin "1") (pinfunction "1_1") (pintype "passive"))
      (node (ref "U8") (pin "6") (pinfunction "-IN_6") (pintype "input"))
      (node (ref "U8") (pin "7") (pinfunction "OUT_7") (pintype "output"))
    )
    (net (code "88") (name "Net-(U8C-+IN)") (class "Default")
      (node (ref "C48") (pin "1") (pinfunction "1_1") (pintype "passive"))
      (node (ref "R32") (pin "2") (pinfunction "2_2") (pintype "passive"))
      (node (ref "U8") (pin "10") (pinfunction "+IN_10") (pintype "input"))
    )
    (net (code "89") (name "Net-(U8D-+IN)") (class "Default")
      (node (ref "C46") (pin "1") (pinfunction "1_1") (pintype "passive"))
      (node (ref "R30") (pin "2") (pinfunction "2_2") (pintype "passive"))
      (node (ref "U8") (pin "12") (pinfunction "+IN_12") (pintype "input"))
    )
    (net (code "90") (name "PAS1") (class "Default")
      (node (ref "C17") (pin "1") (pinfunction "1_1") (pintype "passive"))
      (node (ref "C25") (pin "1") (pinfunction "1_1") (pintype "passive"))
      (node (ref "C41") (pin "1") (pinfunction "1_1") (pintype "passive"))
      (node (ref "C5") (pin "1") (pinfunction "1_1") (pintype "passive"))
      (node (ref "JP13") (pin "2") (pinfunction "2_2") (pintype "passive"))
      (node (ref "JP15") (pin "2") (pinfunction "2_2") (pintype "passive"))
      (node (ref "JP3") (pin "2") (pinfunction "2_2") (pintype "passive"))
      (node (ref "JP9") (pin "2") (pinfunction "2_2") (pintype "passive"))
      (node (ref "R19") (pin "2") (pinfunction "2_2") (pintype "passive"))
      (node (ref "R27") (pin "2") (pinfunction "2_2") (pintype "passive"))
      (node (ref "R3") (pin "2") (pinfunction "2_2") (pintype "passive"))
      (node (ref "R9") (pin "2") (pinfunction "2_2") (pintype "passive"))
      (node (ref "U1") (pin "5") (pinfunction "+IN_5") (pintype "input"))
      (node (ref "U2") (pin "5") (pinfunction "+IN_5") (pintype "input"))
      (node (ref "U5") (pin "5") (pinfunction "+IN_5") (pintype "input"))
      (node (ref "U7") (pin "5") (pinfunction "+IN_5") (pintype "input"))
    )
    (net (code "91") (name "PAS2") (class "Default")
      (node (ref "C11") (pin "1") (pinfunction "1_1") (pintype "passive"))
      (node (ref "C31") (pin "1") (pinfunction "1_1") (pintype "passive"))
      (node (ref "C35") (pin "1") (pinfunction "1_1") (pintype "passive"))
      (node (ref "C47") (pin "1") (pinfunction "1_1") (pintype "passive"))
      (node (ref "JP10") (pin "2") (pinfunction "2_2") (pintype "passive"))
      (node (ref "JP14") (pin "2") (pinfunction "2_2") (pintype "passive"))
      (node (ref "JP16") (pin "2") (pinfunction "2_2") (pintype "passive"))
      (node (ref "JP4") (pin "2") (pinfunction "2_2") (pintype "passive"))
      (node (ref "R13") (pin "2") (pinfunction "2_2") (pintype "passive"))
      (node (ref "R15") (pin "2") (pinfunction "2_2") (pintype "passive"))
      (node (ref "R23") (pin "2") (pinfunction "2_2") (pintype "passive"))
      (node (ref "R31") (pin "2") (pinfunction "2_2") (pintype "passive"))
      (node (ref "U3") (pin "5") (pinfunction "+IN_5") (pintype "input"))
      (node (ref "U4") (pin "5") (pinfunction "+IN_5") (pintype "input"))
      (node (ref "U6") (pin "5") (pinfunction "+IN_5") (pintype "input"))
      (node (ref "U8") (pin "5") (pinfunction "+IN_5") (pintype "input"))
    )
    (net (code "92") (name "VCC") (class "Default")
      (node (ref "C14") (pin "1") (pinfunction "1_1") (pintype "passive"))
      (node (ref "C2") (pin "1") (pinfunction "1_1") (pintype "passive"))
      (node (ref "C20") (pin "1") (pinfunction "1_1") (pintype "passive"))
      (node (ref "C22") (pin "1") (pinfunction "1_1") (pintype "passive"))
      (node (ref "C27") (pin "1") (pinfunction "1_1") (pintype "passive"))
      (node (ref "C38") (pin "1") (pinfunction "1_1") (pintype "passive"))
      (node (ref "C44") (pin "1") (pinfunction "1_1") (pintype "passive"))
      (node (ref "C8") (pin "1") (pinfunction "1_1") (pintype "passive"))
      (node (ref "U1") (pin "4") (pinfunction "V+_4") (pintype "power_in"))
      (node (ref "U2") (pin "4") (pinfunction "V+_4") (pintype "power_in"))
      (node (ref "U3") (pin "4") (pinfunction "V+_4") (pintype "power_in"))
      (node (ref "U4") (pin "4") (pinfunction "V+_4") (pintype "power_in"))
      (node (ref "U5") (pin "4") (pinfunction "V+_4") (pintype "power_in"))
      (node (ref "U6") (pin "4") (pinfunction "V+_4") (pintype "power_in"))
      (node (ref "U7") (pin "4") (pinfunction "V+_4") (pintype "power_in"))
      (node (ref "U8") (pin "4") (pinfunction "V+_4") (pintype "power_in"))
    )
    (net (code "93") (name "VSS") (class "Default")
      (node (ref "C15") (pin "1") (pinfunction "1_1") (pintype "passive"))
      (node (ref "C23") (pin "1") (pinfunction "1_1") (pintype "passive"))
      (node (ref "C29") (pin "1") (pinfunction "1_1") (pintype "passive"))
      (node (ref "C3") (pin "1") (pinfunction "1_1") (pintype "passive"))
      (node (ref "C33") (pin "1") (pinfunction "1_1") (pintype "passive"))
      (node (ref "C39") (pin "1") (pinfunction "1_1") (pintype "passive"))
      (node (ref "C45") (pin "1") (pinfunction "1_1") (pintype "passive"))
      (node (ref "C9") (pin "1") (pinfunction "1_1") (pintype "passive"))
      (node (ref "U1") (pin "11") (pinfunction "V-_11") (pintype "power_in"))
      (node (ref "U2") (pin "11") (pinfunction "V-_11") (pintype "power_in"))
      (node (ref "U3") (pin "11") (pinfunction "V-_11") (pintype "power_in"))
      (node (ref "U4") (pin "11") (pinfunction "V-_11") (pintype "power_in"))
      (node (ref "U5") (pin "11") (pinfunction "V-_11") (pintype "power_in"))
      (node (ref "U6") (pin "11") (pinfunction "V-_11") (pintype "power_in"))
      (node (ref "U7") (pin "11") (pinfunction "V-_11") (pintype "power_in"))
      (node (ref "U8") (pin "11") (pinfunction "V-_11") (pintype "power_in"))
    )
  )
)
